# gen13.net
KiCad netlist of a schematic drawn in EAGLE
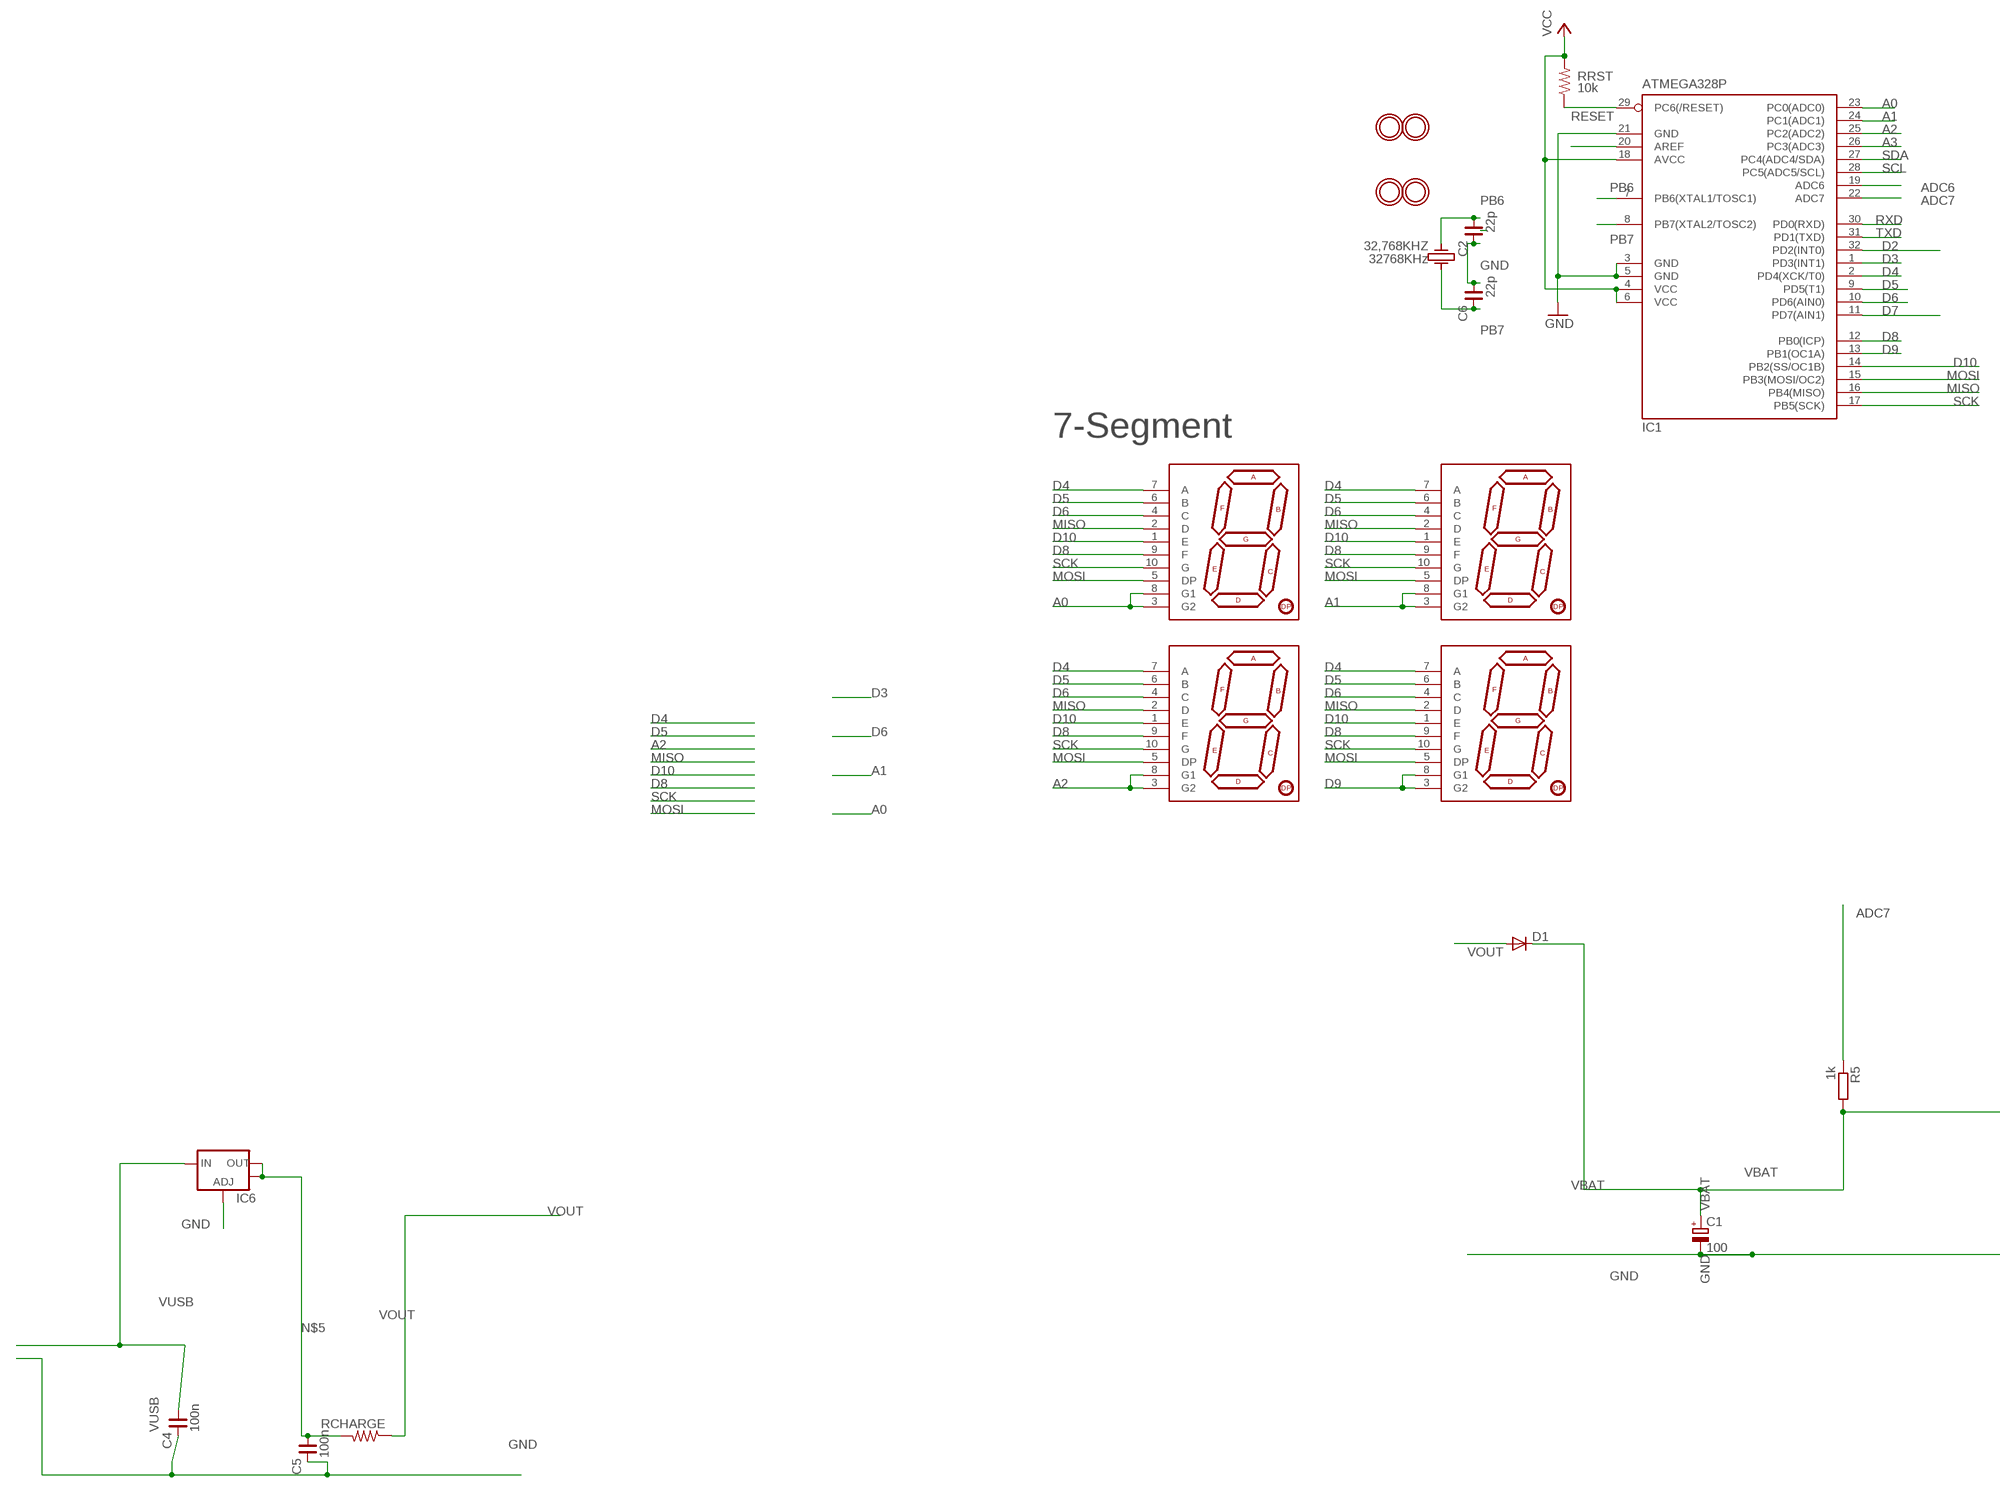
[diagram p0: schematic, sheet 1, part 1 of 2]
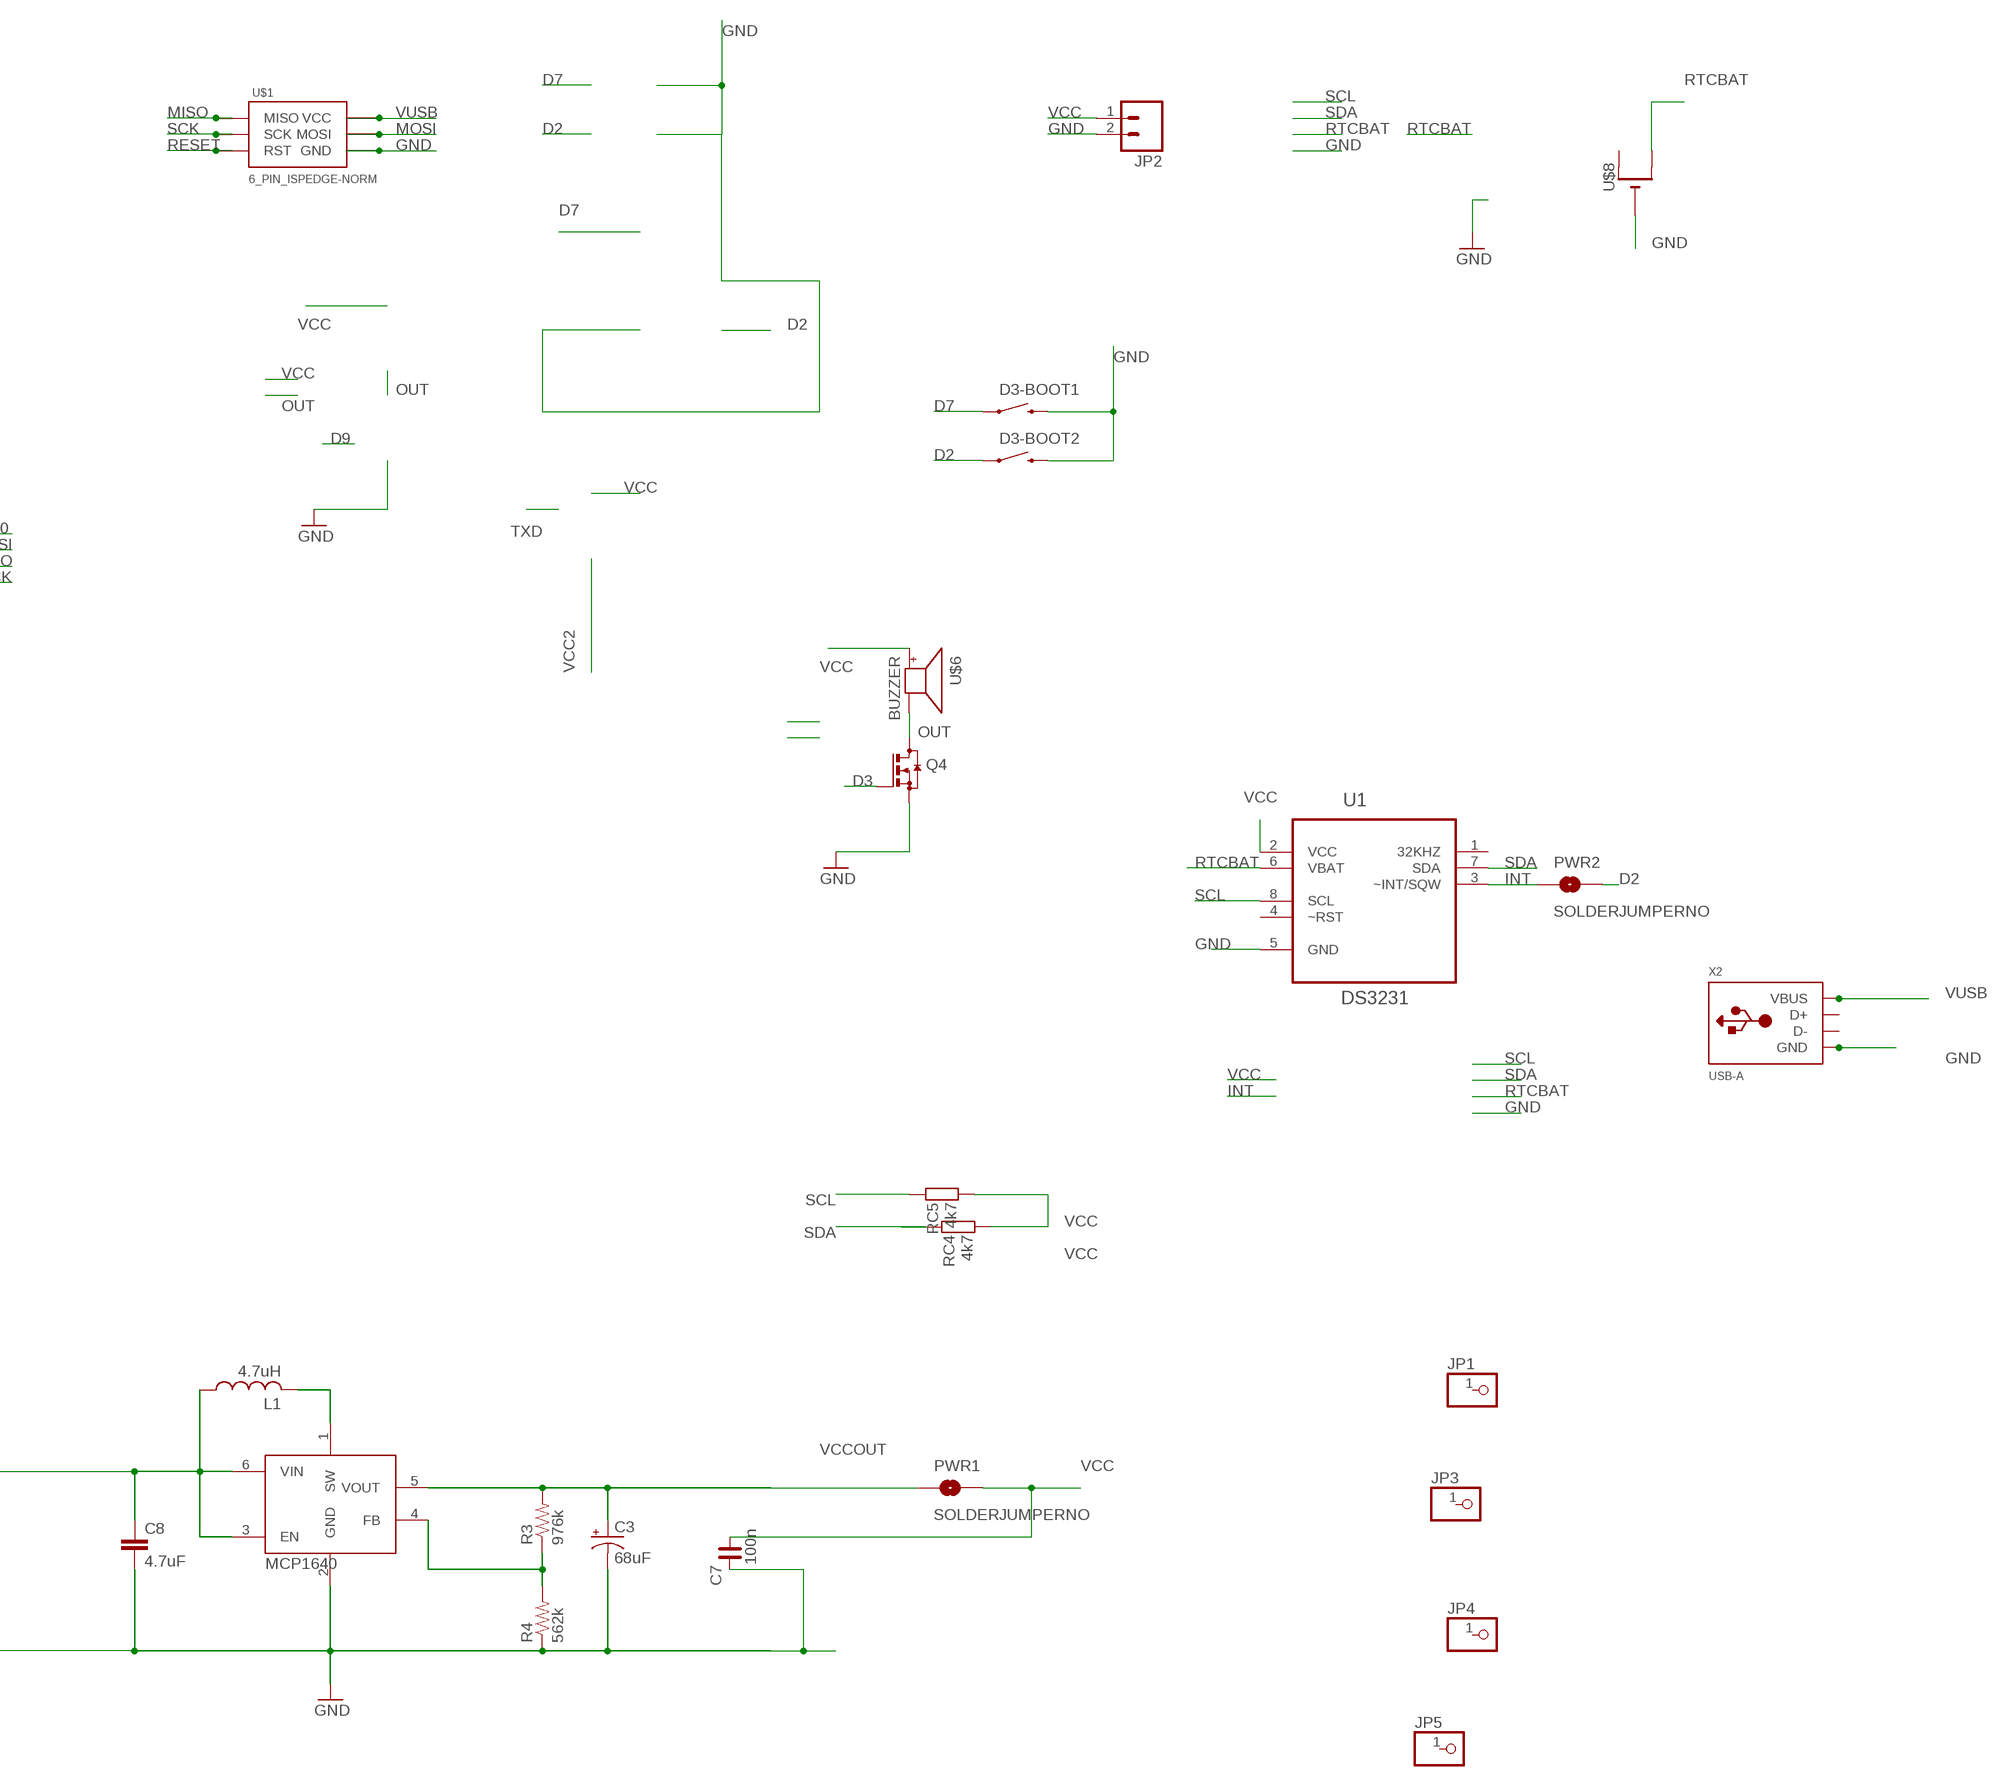
[diagram p1: schematic, sheet 1, part 2 of 2]

(export (version "E")
  (design (tool "Eeschema 10.0.6"))
  (components
    (comp (ref "32,768KHZ")
      (value "32768KHz")
      (footprint "eagle-import:KX-327LT")
      (libsource (lib "eagle-import") (part "CRYSTALL"))
    )
    (comp (ref "C1")
      (value "100")
      (footprint "eagle-import:TT2D4")
      (libsource (lib "eagle-import") (part "CPOL-EUTT2D4"))
    )
    (comp (ref "C2")
      (value "22p")
      (footprint "eagle-import:C0603")
      (libsource (lib "eagle-import") (part "C_0603"))
    )
    (comp (ref "C3")
      (value "68uF")
      (footprint "eagle-import:EIA3216")
      (libsource (lib "eagle-import") (part "CAP_POL1206"))
    )
    (comp (ref "C4")
      (value "100n")
      (footprint "eagle-import:C0603")
      (libsource (lib "eagle-import") (part "C_0603"))
    )
    (comp (ref "C5")
      (value "100n")
      (footprint "eagle-import:C0603")
      (libsource (lib "eagle-import") (part "C_0603"))
    )
    (comp (ref "C6")
      (value "22p")
      (footprint "eagle-import:C0603")
      (libsource (lib "eagle-import") (part "C_0603"))
    )
    (comp (ref "C7")
      (value "100n")
      (footprint "eagle-import:C0603")
      (libsource (lib "eagle-import") (part "C_0603"))
    )
    (comp (ref "C8")
      (value "4.7uF")
      (footprint "eagle-import:0805")
      (libsource (lib "eagle-import") (part "CAP0805"))
    )
    (comp (ref "D1")
      (value "DIODE-DO214AC")
      (footprint "eagle-import:DO214AC")
      (libsource (lib "eagle-import") (part "DIODE-DO214AC"))
    )
    (comp (ref "D3-BOOT1")
      (value "SWITCH-MOMENTARY-2-SMD-1101NE")
      (footprint "eagle-import:TACTILE-SWITCH-1101NE")
      (libsource (lib "eagle-import") (part "SWITCH-MOMENTARY-2-SMD-1101NE"))
    )
    (comp (ref "D3-BOOT2")
      (value "SWITCH-MOMENTARY-2-SMD-1101NE")
      (footprint "eagle-import:TACTILE-SWITCH-1101NE")
      (libsource (lib "eagle-import") (part "SWITCH-MOMENTARY-2-SMD-1101NE"))
    )
    (comp (ref "DIG1")
      (value "7-SEGMENT-DISPLAY-1\"-RED")
      (footprint "eagle-import:7-SEGMENT-SMD")
      (libsource (lib "eagle-import") (part "7-SEGMENT-DISPLAY-1{dblquote}-RED"))
    )
    (comp (ref "DIG2")
      (value "7-SEGMENT-DISPLAY-1\"-RED")
      (footprint "eagle-import:7-SEGMENT-SMD")
      (libsource (lib "eagle-import") (part "7-SEGMENT-DISPLAY-1{dblquote}-RED"))
    )
    (comp (ref "DIG3")
      (value "7-SEGMENT-DISPLAY-1\"-RED")
      (footprint "eagle-import:7-SEGMENT-SMD")
      (libsource (lib "eagle-import") (part "7-SEGMENT-DISPLAY-1{dblquote}-RED"))
    )
    (comp (ref "DIG4")
      (value "7-SEGMENT-DISPLAY-1\"-RED")
      (footprint "eagle-import:7-SEGMENT-SMD")
      (libsource (lib "eagle-import") (part "7-SEGMENT-DISPLAY-1{dblquote}-RED"))
    )
    (comp (ref "IC1")
      (value "ATMEGA328P")
      (footprint "eagle-import:TQFP32-08")
      (fields (field (name "MPN") "ATMEGA8-16AU"))
      (libsource (lib "eagle-import") (part "MEGA8-AI"))
    )
    (comp (ref "IC6")
      (value "V_REG_LM1117SOT223")
      (footprint "eagle-import:SOT223")
      (libsource (lib "eagle-import") (part "V_REG_LM1117SOT223"))
    )
    (comp (ref "JP1")
      (value "PINHD-1X1")
      (footprint "eagle-import:1X01")
      (libsource (lib "eagle-import") (part "PINHD-1X1"))
    )
    (comp (ref "JP2")
      (value "M02PTH")
      (footprint "eagle-import:1X02")
      (libsource (lib "eagle-import") (part "M02PTH"))
    )
    (comp (ref "JP3")
      (value "PINHD-1X1")
      (footprint "eagle-import:1X01")
      (libsource (lib "eagle-import") (part "PINHD-1X1"))
    )
    (comp (ref "JP4")
      (value "PINHD-1X1")
      (footprint "eagle-import:1X01")
      (libsource (lib "eagle-import") (part "PINHD-1X1"))
    )
    (comp (ref "JP5")
      (value "PINHD-1X1")
      (footprint "eagle-import:1X01")
      (libsource (lib "eagle-import") (part "PINHD-1X1"))
    )
    (comp (ref "L1")
      (value "4.7uH")
      (footprint "eagle-import:LQH44")
      (libsource (lib "eagle-import") (part "LLQH44P_P0"))
    )
    (comp (ref "PWR1")
      (value "SOLDERJUMPERNO")
      (footprint "eagle-import:SJ_2S-NO")
      (libsource (lib "eagle-import") (part "SOLDERJUMPERNO"))
    )
    (comp (ref "PWR2")
      (value "SOLDERJUMPERNO")
      (footprint "eagle-import:SJ_2S-NO")
      (libsource (lib "eagle-import") (part "SOLDERJUMPERNO"))
    )
    (comp (ref "Q4")
      (value "BSS123")
      (footprint "eagle-import:SOT23")
      (libsource (lib "eagle-import") (part "BSS123"))
    )
    (comp (ref "R3")
      (value "976k")
      (footprint "eagle-import:0603-RES")
      (libsource (lib "eagle-import") (part "RESISTOR0603-RES"))
    )
    (comp (ref "R4")
      (value "562k")
      (footprint "eagle-import:0603-RES")
      (libsource (lib "eagle-import") (part "RESISTOR0603-RES"))
    )
    (comp (ref "R5")
      (value "1k")
      (footprint "eagle-import:R0603")
      (libsource (lib "eagle-import") (part "R-EU_R0603"))
    )
    (comp (ref "RC4")
      (value "4k7")
      (footprint "eagle-import:R0603")
      (libsource (lib "eagle-import") (part "R-EU_R0603"))
    )
    (comp (ref "RC5")
      (value "4k7")
      (footprint "eagle-import:R0603")
      (libsource (lib "eagle-import") (part "R-EU_R0603"))
    )
    (comp (ref "RCHARGE")
      (value "RESISTOR1206")
      (footprint "eagle-import:1206")
      (libsource (lib "eagle-import") (part "RESISTOR1206"))
    )
    (comp (ref "RRST")
      (value "10k")
      (footprint "eagle-import:R0603@1")
      (libsource (lib "eagle-import") (part "R-US_R0603"))
    )
    (comp (ref "U$1")
      (value "6_PIN_ISPEDGE-NORM")
      (footprint "eagle-import:6_PIN_EDGE")
      (libsource (lib "eagle-import") (part "6_PIN_ISPEDGE-NORM"))
    )
    (comp (ref "U$2")
      (value "MOUNTINGHOLE2.0")
      (footprint "eagle-import:MOUNTINGHOLE_2.0_PLATED")
      (libsource (lib "eagle-import") (part "MOUNTINGHOLE2.0"))
    )
    (comp (ref "U$3")
      (value "MOUNTINGHOLE2.0")
      (footprint "eagle-import:MOUNTINGHOLE_2.0_PLATED")
      (libsource (lib "eagle-import") (part "MOUNTINGHOLE2.0"))
    )
    (comp (ref "U$4")
      (value "MOUNTINGHOLE2.0")
      (footprint "eagle-import:MOUNTINGHOLE_2.0_PLATED")
      (libsource (lib "eagle-import") (part "MOUNTINGHOLE2.0"))
    )
    (comp (ref "U$5")
      (value "MOUNTINGHOLE2.0")
      (footprint "eagle-import:MOUNTINGHOLE_2.0_PLATED")
      (libsource (lib "eagle-import") (part "MOUNTINGHOLE2.0"))
    )
    (comp (ref "U$6")
      (value "BUZZER")
      (footprint "eagle-import:SMT-8585-BUZZER")
      (libsource (lib "eagle-import") (part "BUZZER"))
    )
    (comp (ref "U$8")
      (value "CR1220SMT")
      (footprint "eagle-import:CR1220-SMD")
      (libsource (lib "eagle-import") (part "CR1220SMT"))
    )
    (comp (ref "U1")
      (value "DS3231")
      (footprint "eagle-import:SOIC8_150MIL")
      (libsource (lib "eagle-import") (part "DS3231MZ+"))
    )
    (comp (ref "U2")
      (value "MCP1640")
      (footprint "eagle-import:SOT23-6")
      (libsource (lib "eagle-import") (part "MCP1640"))
    )
    (comp (ref "X2")
      (value "USB-A")
      (footprint "eagle-import:MOLEX_480371000")
      (libsource (lib "eagle-import") (part "USB-A"))
    )
  )
  (nets
    (net (code "1") (name "/A0") (class "Default")
      (node (ref "DIG1") (pin "3") (pinfunction "G2_3") (pintype "bidirectional"))
      (node (ref "DIG1") (pin "8") (pinfunction "G1_8") (pintype "bidirectional"))
      (node (ref "IC1") (pin "23") (pinfunction "PC0(ADC0)_23") (pintype "bidirectional"))
    )
    (net (code "2") (name "/A1") (class "Default")
      (node (ref "DIG2") (pin "3") (pinfunction "G2_3") (pintype "bidirectional"))
      (node (ref "DIG2") (pin "8") (pinfunction "G1_8") (pintype "bidirectional"))
      (node (ref "IC1") (pin "24") (pinfunction "PC1(ADC1)_24") (pintype "bidirectional"))
    )
    (net (code "3") (name "/A2") (class "Default")
      (node (ref "DIG3") (pin "3") (pinfunction "G2_3") (pintype "bidirectional"))
      (node (ref "DIG3") (pin "8") (pinfunction "G1_8") (pintype "bidirectional"))
      (node (ref "IC1") (pin "25") (pinfunction "PC2(ADC2)_25") (pintype "bidirectional"))
    )
    (net (code "4") (name "/A3") (class "Default")
      (node (ref "IC1") (pin "26") (pinfunction "PC3(ADC3)_26") (pintype "bidirectional"))
    )
    (net (code "5") (name "/ADC6") (class "Default")
      (node (ref "IC1") (pin "19") (pinfunction "ADC6_19") (pintype "bidirectional"))
    )
    (net (code "6") (name "/ADC7") (class "Default")
      (node (ref "IC1") (pin "22") (pinfunction "ADC7_22") (pintype "bidirectional"))
      (node (ref "R5") (pin "1") (pinfunction "1_1") (pintype "passive"))
    )
    (net (code "7") (name "/D2") (class "Default")
      (node (ref "D3-BOOT2") (pin "P$1") (pinfunction "1_P$1") (pintype "passive"))
      (node (ref "IC1") (pin "32") (pinfunction "PD2(INT0)_32") (pintype "bidirectional"))
      (node (ref "PWR2") (pin "2") (pinfunction "2_2") (pintype "passive"))
    )
    (net (code "8") (name "/D3") (class "Default")
      (node (ref "IC1") (pin "1") (pinfunction "PD3(INT1)_1") (pintype "bidirectional"))
      (node (ref "Q4") (pin "1") (pinfunction "G_1") (pintype "passive"))
    )
    (net (code "9") (name "/D4") (class "Default")
      (node (ref "DIG1") (pin "7") (pinfunction "A_7") (pintype "bidirectional"))
      (node (ref "DIG2") (pin "7") (pinfunction "A_7") (pintype "bidirectional"))
      (node (ref "DIG3") (pin "7") (pinfunction "A_7") (pintype "bidirectional"))
      (node (ref "DIG4") (pin "7") (pinfunction "A_7") (pintype "bidirectional"))
      (node (ref "IC1") (pin "2") (pinfunction "PD4(XCK/T0)_2") (pintype "bidirectional"))
    )
    (net (code "10") (name "/D5") (class "Default")
      (node (ref "DIG1") (pin "6") (pinfunction "B_6") (pintype "bidirectional"))
      (node (ref "DIG2") (pin "6") (pinfunction "B_6") (pintype "bidirectional"))
      (node (ref "DIG3") (pin "6") (pinfunction "B_6") (pintype "bidirectional"))
      (node (ref "DIG4") (pin "6") (pinfunction "B_6") (pintype "bidirectional"))
      (node (ref "IC1") (pin "9") (pinfunction "PD5(T1)_9") (pintype "bidirectional"))
    )
    (net (code "11") (name "/D6") (class "Default")
      (node (ref "DIG1") (pin "4") (pinfunction "C_4") (pintype "bidirectional"))
      (node (ref "DIG2") (pin "4") (pinfunction "C_4") (pintype "bidirectional"))
      (node (ref "DIG3") (pin "4") (pinfunction "C_4") (pintype "bidirectional"))
      (node (ref "DIG4") (pin "4") (pinfunction "C_4") (pintype "bidirectional"))
      (node (ref "IC1") (pin "10") (pinfunction "PD6(AIN0)_10") (pintype "bidirectional"))
    )
    (net (code "12") (name "/D7") (class "Default")
      (node (ref "D3-BOOT1") (pin "P$1") (pinfunction "1_P$1") (pintype "passive"))
      (node (ref "IC1") (pin "11") (pinfunction "PD7(AIN1)_11") (pintype "bidirectional"))
    )
    (net (code "13") (name "/D8") (class "Default")
      (node (ref "DIG1") (pin "9") (pinfunction "F_9") (pintype "bidirectional"))
      (node (ref "DIG2") (pin "9") (pinfunction "F_9") (pintype "bidirectional"))
      (node (ref "DIG3") (pin "9") (pinfunction "F_9") (pintype "bidirectional"))
      (node (ref "DIG4") (pin "9") (pinfunction "F_9") (pintype "bidirectional"))
      (node (ref "IC1") (pin "12") (pinfunction "PB0(ICP)_12") (pintype "bidirectional"))
    )
    (net (code "14") (name "/D9") (class "Default")
      (node (ref "DIG4") (pin "3") (pinfunction "G2_3") (pintype "bidirectional"))
      (node (ref "DIG4") (pin "8") (pinfunction "G1_8") (pintype "bidirectional"))
      (node (ref "IC1") (pin "13") (pinfunction "PB1(OC1A)_13") (pintype "bidirectional"))
    )
    (net (code "15") (name "/D10") (class "Default")
      (node (ref "DIG1") (pin "1") (pinfunction "E_1") (pintype "bidirectional"))
      (node (ref "DIG2") (pin "1") (pinfunction "E_1") (pintype "bidirectional"))
      (node (ref "DIG3") (pin "1") (pinfunction "E_1") (pintype "bidirectional"))
      (node (ref "DIG4") (pin "1") (pinfunction "E_1") (pintype "bidirectional"))
      (node (ref "IC1") (pin "14") (pinfunction "PB2(SS/OC1B)_14") (pintype "bidirectional"))
    )
    (net (code "16") (name "/INT") (class "Default")
      (node (ref "PWR2") (pin "1") (pinfunction "1_1") (pintype "passive"))
      (node (ref "U1") (pin "3") (pinfunction "~{INT/SQW}_3") (pintype "output"))
    )
    (net (code "17") (name "/MISO") (class "Default")
      (node (ref "DIG1") (pin "2") (pinfunction "D_2") (pintype "bidirectional"))
      (node (ref "DIG2") (pin "2") (pinfunction "D_2") (pintype "bidirectional"))
      (node (ref "DIG3") (pin "2") (pinfunction "D_2") (pintype "bidirectional"))
      (node (ref "DIG4") (pin "2") (pinfunction "D_2") (pintype "bidirectional"))
      (node (ref "IC1") (pin "16") (pinfunction "PB4(MISO)_16") (pintype "bidirectional"))
      (node (ref "U$1") (pin "1") (pinfunction "MISO_1") (pintype "bidirectional"))
    )
    (net (code "18") (name "/MOSI") (class "Default")
      (node (ref "DIG1") (pin "5") (pinfunction "DP_5") (pintype "bidirectional"))
      (node (ref "DIG2") (pin "5") (pinfunction "DP_5") (pintype "bidirectional"))
      (node (ref "DIG3") (pin "5") (pinfunction "DP_5") (pintype "bidirectional"))
      (node (ref "DIG4") (pin "5") (pinfunction "DP_5") (pintype "bidirectional"))
      (node (ref "IC1") (pin "15") (pinfunction "PB3(MOSI/OC2)_15") (pintype "bidirectional"))
      (node (ref "U$1") (pin "4") (pinfunction "MOSI_4") (pintype "bidirectional"))
    )
    (net (code "19") (name "/N$5") (class "Default")
      (node (ref "C5") (pin "1") (pinfunction "1_1") (pintype "passive"))
      (node (ref "IC6") (pin "2") (pinfunction "OUT_2") (pintype "output"))
      (node (ref "IC6") (pin "4") (pinfunction "OUT_4") (pintype "output"))
      (node (ref "RCHARGE") (pin "2") (pinfunction "2_2") (pintype "passive"))
    )
    (net (code "20") (name "/OUT") (class "Default")
      (node (ref "Q4") (pin "3") (pinfunction "D_3") (pintype "passive"))
      (node (ref "U$6") (pin "-") (pinfunction "-_-") (pintype "passive"))
    )
    (net (code "21") (name "/PB6") (class "Default")
      (node (ref "32,768KHZ") (pin "4") (pinfunction "P$2_4") (pintype "bidirectional"))
      (node (ref "C2") (pin "1") (pinfunction "1_1") (pintype "passive"))
      (node (ref "IC1") (pin "7") (pinfunction "PB6(XTAL1/TOSC1)_7") (pintype "bidirectional"))
    )
    (net (code "22") (name "/PB7") (class "Default")
      (node (ref "32,768KHZ") (pin "1") (pinfunction "P$1_1") (pintype "bidirectional"))
      (node (ref "C6") (pin "2") (pinfunction "2_2") (pintype "passive"))
      (node (ref "IC1") (pin "8") (pinfunction "PB7(XTAL2/TOSC2)_8") (pintype "bidirectional"))
    )
    (net (code "23") (name "/RESET") (class "Default")
      (node (ref "IC1") (pin "29") (pinfunction "PC6(/RESET)_29") (pintype "bidirectional"))
      (node (ref "RRST") (pin "1") (pinfunction "1_1") (pintype "passive"))
      (node (ref "U$1") (pin "5") (pinfunction "RST_5") (pintype "bidirectional"))
    )
    (net (code "24") (name "/RTCBAT") (class "Default")
      (node (ref "U$8") (pin "+$2") (pinfunction "+1_+$2") (pintype "passive"))
      (node (ref "U1") (pin "6") (pinfunction "VBAT_6") (pintype "power_in"))
    )
    (net (code "25") (name "/RXD") (class "Default")
      (node (ref "IC1") (pin "30") (pinfunction "PD0(RXD)_30") (pintype "bidirectional"))
    )
    (net (code "26") (name "/SCK") (class "Default")
      (node (ref "DIG1") (pin "10") (pinfunction "G_10") (pintype "bidirectional"))
      (node (ref "DIG2") (pin "10") (pinfunction "G_10") (pintype "bidirectional"))
      (node (ref "DIG3") (pin "10") (pinfunction "G_10") (pintype "bidirectional"))
      (node (ref "DIG4") (pin "10") (pinfunction "G_10") (pintype "bidirectional"))
      (node (ref "IC1") (pin "17") (pinfunction "PB5(SCK)_17") (pintype "bidirectional"))
      (node (ref "U$1") (pin "3") (pinfunction "SCK_3") (pintype "bidirectional"))
    )
    (net (code "27") (name "/SCL") (class "Default")
      (node (ref "IC1") (pin "28") (pinfunction "PC5(ADC5/SCL)_28") (pintype "bidirectional"))
      (node (ref "RC5") (pin "2") (pinfunction "2_2") (pintype "passive"))
      (node (ref "U1") (pin "8") (pinfunction "SCL_8") (pintype "input"))
    )
    (net (code "28") (name "/SDA") (class "Default")
      (node (ref "IC1") (pin "27") (pinfunction "PC4(ADC4/SDA)_27") (pintype "bidirectional"))
      (node (ref "RC4") (pin "2") (pinfunction "2_2") (pintype "passive"))
      (node (ref "U1") (pin "7") (pinfunction "SDA_7") (pintype "bidirectional"))
    )
    (net (code "29") (name "/TXD") (class "Default")
      (node (ref "IC1") (pin "31") (pinfunction "PD1(TXD)_31") (pintype "bidirectional"))
    )
    (net (code "30") (name "/VBAT") (class "Default")
      (node (ref "C1") (pin "+") (pinfunction "+_+") (pintype "passive"))
      (node (ref "C8") (pin "1") (pinfunction "1_1") (pintype "passive"))
      (node (ref "D1") (pin "C") (pinfunction "C_C") (pintype "passive"))
      (node (ref "L1") (pin "P$1") (pinfunction "1_P$1") (pintype "passive"))
      (node (ref "R5") (pin "2") (pinfunction "2_2") (pintype "passive"))
      (node (ref "U2") (pin "3") (pinfunction "EN_3") (pintype "input"))
      (node (ref "U2") (pin "6") (pinfunction "VIN_6") (pintype "input"))
    )
    (net (code "32") (name "/VCCOUT") (class "Default")
      (node (ref "C3") (pin "A") (pinfunction "+_A") (pintype "passive"))
      (node (ref "PWR1") (pin "1") (pinfunction "1_1") (pintype "passive"))
      (node (ref "R3") (pin "2") (pinfunction "2_2") (pintype "passive"))
      (node (ref "U2") (pin "5") (pinfunction "VOUT_5") (pintype "output"))
    )
    (net (code "33") (name "/VOUT") (class "Default")
      (node (ref "D1") (pin "A") (pinfunction "A_A") (pintype "passive"))
      (node (ref "RCHARGE") (pin "1") (pinfunction "1_1") (pintype "passive"))
    )
    (net (code "34") (name "/VUSB") (class "Default")
      (node (ref "C4") (pin "1") (pinfunction "1_1") (pintype "passive"))
      (node (ref "IC6") (pin "3") (pinfunction "IN_3") (pintype "input"))
      (node (ref "U$1") (pin "2") (pinfunction "VCC_2") (pintype "power_in"))
      (node (ref "X2") (pin "1") (pinfunction "VBUS_1") (pintype "power_in"))
    )
    (net (code "35") (name "GND") (class "Default")
      (node (ref "C1") (pin "-") (pinfunction "-_-") (pintype "passive"))
      (node (ref "C2") (pin "2") (pinfunction "2_2") (pintype "passive"))
      (node (ref "C3") (pin "C") (pinfunction "-_C") (pintype "passive"))
      (node (ref "C4") (pin "2") (pinfunction "2_2") (pintype "passive"))
      (node (ref "C5") (pin "2") (pinfunction "2_2") (pintype "passive"))
      (node (ref "C6") (pin "1") (pinfunction "1_1") (pintype "passive"))
      (node (ref "C7") (pin "2") (pinfunction "2_2") (pintype "passive"))
      (node (ref "C8") (pin "2") (pinfunction "2_2") (pintype "passive"))
      (node (ref "D3-BOOT1") (pin "P$2") (pinfunction "2_P$2") (pintype "passive"))
      (node (ref "D3-BOOT2") (pin "P$2") (pinfunction "2_P$2") (pintype "passive"))
      (node (ref "IC1") (pin "21") (pinfunction "GND_21") (pintype "power_in"))
      (node (ref "IC1") (pin "3") (pinfunction "GND_3") (pintype "power_in"))
      (node (ref "IC1") (pin "5") (pinfunction "GND_5") (pintype "power_in"))
      (node (ref "IC6") (pin "1") (pinfunction "ADJ_1") (pintype "input"))
      (node (ref "JP2") (pin "2") (pinfunction "2_2") (pintype "passive"))
      (node (ref "Q4") (pin "2") (pinfunction "S_2") (pintype "passive"))
      (node (ref "R4") (pin "1") (pinfunction "1_1") (pintype "passive"))
      (node (ref "U$1") (pin "6") (pinfunction "GND_6") (pintype "power_in"))
      (node (ref "U$8") (pin "-") (pinfunction "-_-") (pintype "passive"))
      (node (ref "U1") (pin "5") (pinfunction "GND_5") (pintype "passive"))
      (node (ref "U2") (pin "2") (pinfunction "GND_2") (pintype "power_in"))
      (node (ref "X2") (pin "4") (pinfunction "GND_4") (pintype "power_in"))
    )
    (net (code "36") (name "Net-(L1-2)") (class "Default")
      (node (ref "L1") (pin "P$2") (pinfunction "2_P$2") (pintype "passive"))
      (node (ref "U2") (pin "1") (pinfunction "SW_1") (pintype "output"))
    )
    (net (code "37") (name "Net-(U2-FB)") (class "Default")
      (node (ref "R3") (pin "1") (pinfunction "1_1") (pintype "passive"))
      (node (ref "R4") (pin "2") (pinfunction "2_2") (pintype "passive"))
      (node (ref "U2") (pin "4") (pinfunction "FB_4") (pintype "input"))
    )
    (net (code "38") (name "VCC") (class "Default")
      (node (ref "C7") (pin "1") (pinfunction "1_1") (pintype "passive"))
      (node (ref "IC1") (pin "18") (pinfunction "AVCC_18") (pintype "power_in"))
      (node (ref "IC1") (pin "4") (pinfunction "VCC_4") (pintype "power_in"))
      (node (ref "IC1") (pin "6") (pinfunction "VCC_6") (pintype "power_in"))
      (node (ref "JP2") (pin "1") (pinfunction "1_1") (pintype "passive"))
      (node (ref "PWR1") (pin "2") (pinfunction "2_2") (pintype "passive"))
      (node (ref "RC4") (pin "1") (pinfunction "1_1") (pintype "passive"))
      (node (ref "RC5") (pin "1") (pinfunction "1_1") (pintype "passive"))
      (node (ref "RRST") (pin "2") (pinfunction "2_2") (pintype "passive"))
      (node (ref "U$6") (pin "+") (pinfunction "+_+") (pintype "passive"))
      (node (ref "U1") (pin "2") (pinfunction "VCC_2") (pintype "power_in"))
    )
    (net (code "39") (name "unconnected-(IC1-AREF-Pad20)") (class "Default")
      (node (ref "IC1") (pin "20") (pinfunction "AREF_20") (pintype "passive"))
    )
    (net (code "40") (name "unconnected-(JP1-Pad1)") (class "Default")
      (node (ref "JP1") (pin "1") (pinfunction "1_1") (pintype "passive"))
    )
    (net (code "41") (name "unconnected-(JP3-Pad1)") (class "Default")
      (node (ref "JP3") (pin "1") (pinfunction "1_1") (pintype "passive"))
    )
    (net (code "42") (name "unconnected-(JP4-Pad1)") (class "Default")
      (node (ref "JP4") (pin "1") (pinfunction "1_1") (pintype "passive"))
    )
    (net (code "43") (name "unconnected-(JP5-Pad1)") (class "Default")
      (node (ref "JP5") (pin "1") (pinfunction "1_1") (pintype "passive"))
    )
    (net (code "44") (name "unconnected-(U$8-+-Pad+$1)") (class "Default")
      (node (ref "U$8") (pin "+$1") (pinfunction "+_+$1") (pintype "passive"))
    )
    (net (code "45") (name "unconnected-(U1-32KHZ-Pad1)") (class "Default")
      (node (ref "U1") (pin "1") (pinfunction "32KHZ_1") (pintype "output"))
    )
    (net (code "46") (name "unconnected-(U1-~{RST}-Pad4)") (class "Default")
      (node (ref "U1") (pin "4") (pinfunction "~{RST}_4") (pintype "bidirectional"))
    )
    (net (code "47") (name "unconnected-(X2-D+-Pad3)") (class "Default")
      (node (ref "X2") (pin "3") (pinfunction "D+_3") (pintype "bidirectional"))
    )
    (net (code "48") (name "unconnected-(X2-D--Pad2)") (class "Default")
      (node (ref "X2") (pin "2") (pinfunction "D-_2") (pintype "bidirectional"))
    )
  )
)
